# APRS_Pico_with_Baofeng_UV-5R.net
KiCad netlist of a schematic drawn in EAGLE
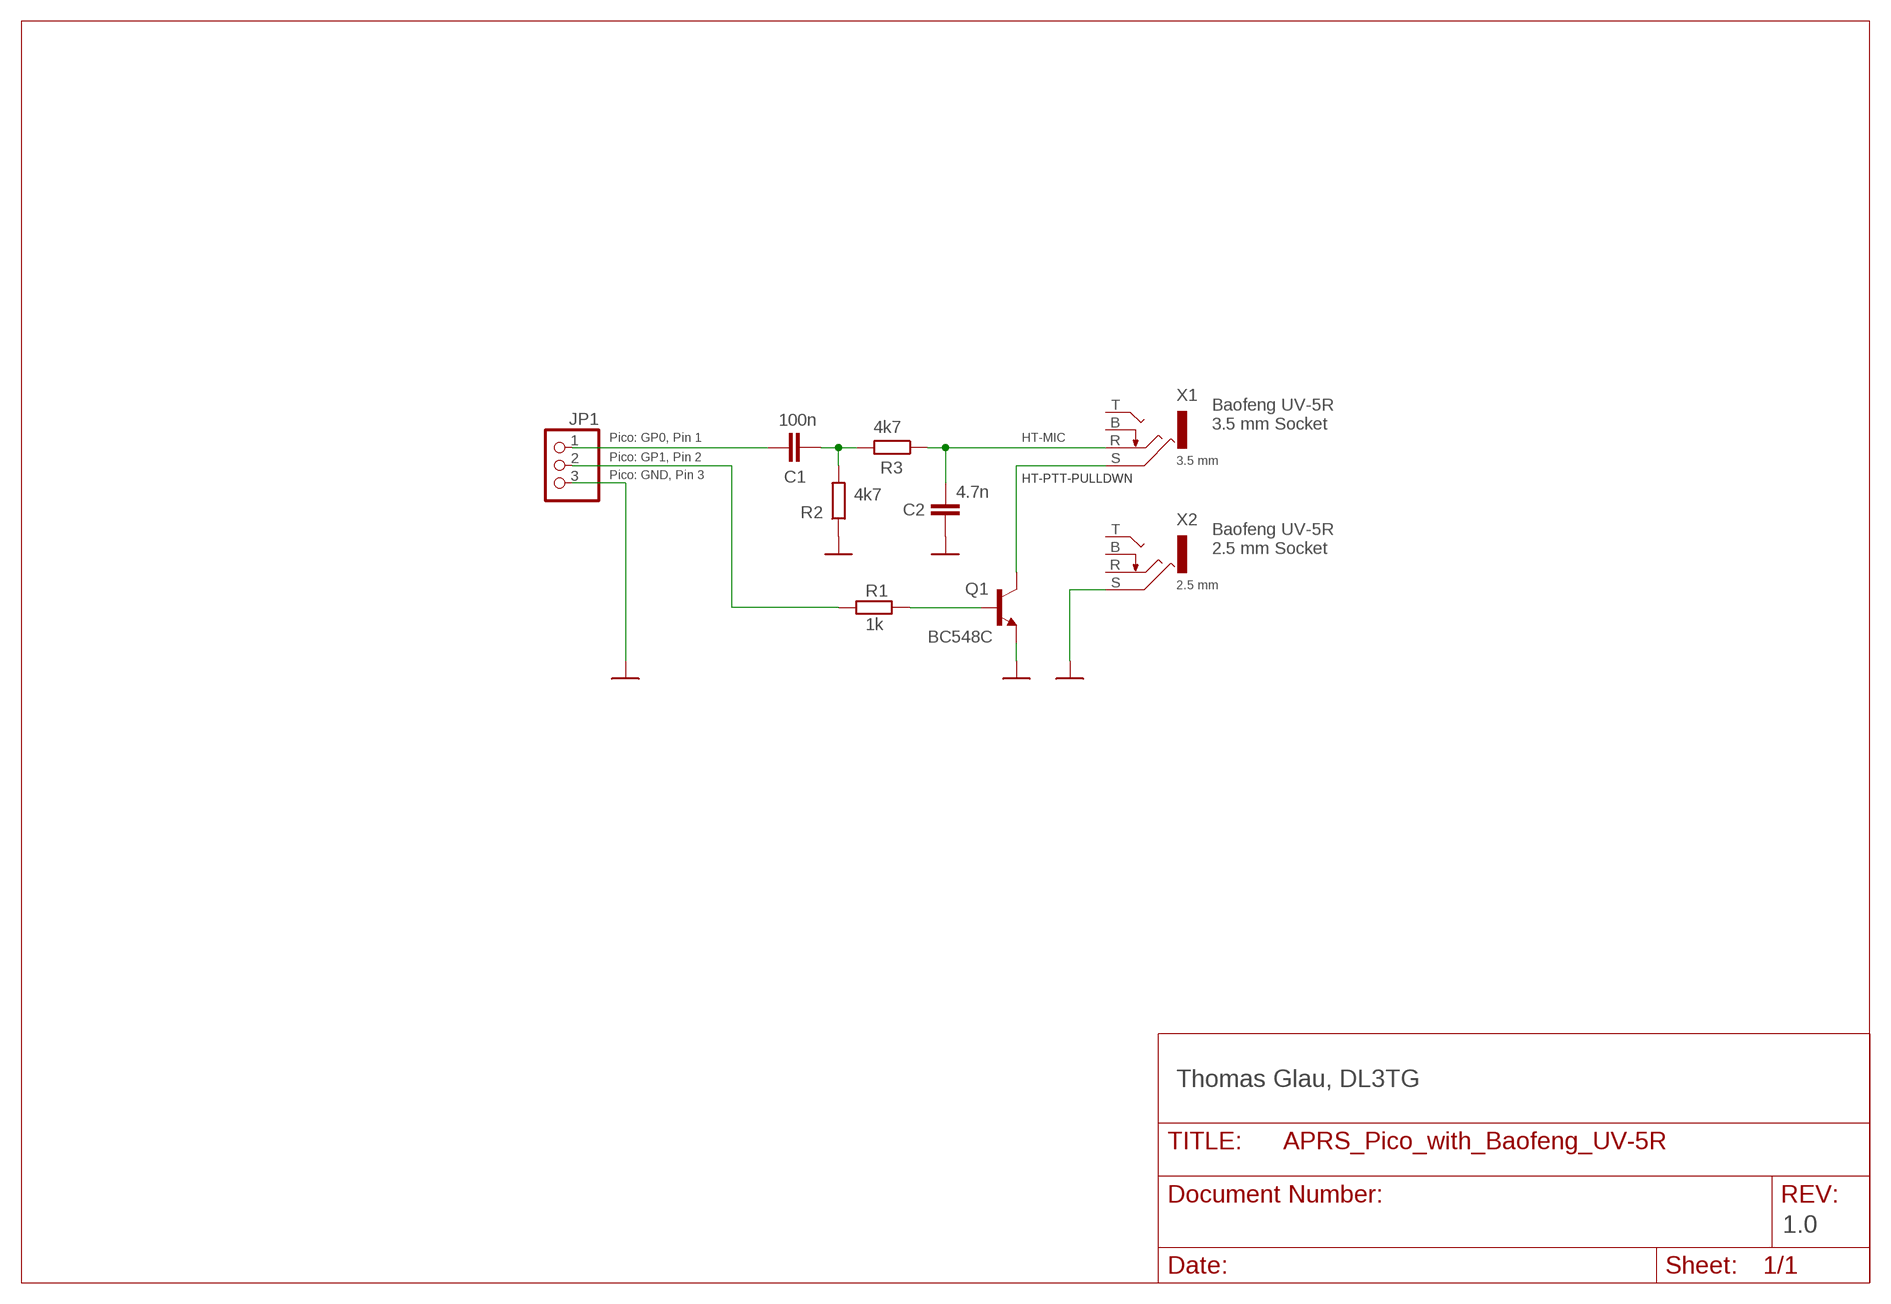
[diagram p0: schematic, sheet 1]

(export (version "E")
  (design (tool "Eeschema 10.0.6"))
  (components
    (comp (ref "C1")
      (value "100n")
      (footprint "eagle-import:C0805")
      (libsource (lib "eagle-import") (part "C"))
    )
    (comp (ref "C2")
      (value "4.7n")
      (footprint "eagle-import:C0805")
      (libsource (lib "eagle-import") (part "C"))
    )
    (comp (ref "JP1")
      (value "PINHD-1X3")
      (footprint "eagle-import:1X03")
      (libsource (lib "eagle-import") (part "PINHD-1X3"))
    )
    (comp (ref "Q1")
      (value "BC548C")
      (footprint "eagle-import:TO92-EBC")
      (libsource (lib "eagle-import") (part "BC548"))
    )
    (comp (ref "R1")
      (value "1k")
      (footprint "eagle-import:0207_10")
      (libsource (lib "eagle-import") (part "R-EU_0207/10"))
    )
    (comp (ref "R2")
      (value "4k7")
      (footprint "eagle-import:R0805")
      (libsource (lib "eagle-import") (part "R"))
    )
    (comp (ref "R3")
      (value "4k7")
      (footprint "eagle-import:R0805")
      (libsource (lib "eagle-import") (part "R"))
    )
    (comp (ref "X1")
      (value "KLBR4")
      (footprint "eagle-import:KLBR4")
      (fields (field (name "MPN") "KLBR 4"))
      (libsource (lib "eagle-import") (part "KLBR4"))
    )
    (comp (ref "X2")
      (value "KLBR4")
      (footprint "eagle-import:KLBR4")
      (fields (field (name "MPN") "KLBR 4"))
      (libsource (lib "eagle-import") (part "KLBR4"))
    )
  )
  (nets
    (net (code "1") (name "/HT-PTT-PULLDWN") (class "Default")
      (node (ref "Q1") (pin "C") (pinfunction "C_C") (pintype "passive"))
      (node (ref "X1") (pin "S") (pinfunction "S_S") (pintype "passive"))
    )
    (net (code "2") (name "GND") (class "Default")
      (node (ref "C2") (pin "1") (pinfunction "1_1") (pintype "passive"))
      (node (ref "JP1") (pin "3") (pinfunction "3_3") (pintype "passive"))
      (node (ref "Q1") (pin "E") (pinfunction "E_E") (pintype "passive"))
      (node (ref "R2") (pin "1") (pinfunction "1_1") (pintype "passive"))
      (node (ref "X2") (pin "S") (pinfunction "S_S") (pintype "passive"))
    )
    (net (code "3") (name "Net-(C1-Pad1)") (class "Default")
      (node (ref "C1") (pin "1") (pinfunction "1_1") (pintype "passive"))
      (node (ref "JP1") (pin "1") (pinfunction "1_1") (pintype "passive"))
    )
    (net (code "4") (name "Net-(C1-Pad2)") (class "Default")
      (node (ref "C1") (pin "2") (pinfunction "2_2") (pintype "passive"))
      (node (ref "R2") (pin "2") (pinfunction "2_2") (pintype "passive"))
      (node (ref "R3") (pin "2") (pinfunction "2_2") (pintype "passive"))
    )
    (net (code "5") (name "Net-(C2-Pad2)") (class "Default")
      (node (ref "C2") (pin "2") (pinfunction "2_2") (pintype "passive"))
      (node (ref "R3") (pin "1") (pinfunction "1_1") (pintype "passive"))
      (node (ref "X1") (pin "R") (pinfunction "R_R") (pintype "passive"))
    )
    (net (code "6") (name "Net-(JP1-Pad2)") (class "Default")
      (node (ref "JP1") (pin "2") (pinfunction "2_2") (pintype "passive"))
      (node (ref "R1") (pin "1") (pinfunction "1_1") (pintype "passive"))
    )
    (net (code "7") (name "Net-(Q1-PadB)") (class "Default")
      (node (ref "Q1") (pin "B") (pinfunction "B_B") (pintype "passive"))
      (node (ref "R1") (pin "2") (pinfunction "2_2") (pintype "passive"))
    )
    (net (code "8") (name "unconnected-(X1-PadB)") (class "Default")
      (node (ref "X1") (pin "B") (pinfunction "B_B") (pintype "passive"))
    )
    (net (code "9") (name "unconnected-(X1-PadT)") (class "Default")
      (node (ref "X1") (pin "T") (pinfunction "T_T") (pintype "passive"))
    )
    (net (code "10") (name "unconnected-(X2-PadB)") (class "Default")
      (node (ref "X2") (pin "B") (pinfunction "B_B") (pintype "passive"))
    )
    (net (code "11") (name "unconnected-(X2-PadR)") (class "Default")
      (node (ref "X2") (pin "R") (pinfunction "R_R") (pintype "passive"))
    )
    (net (code "12") (name "unconnected-(X2-PadT)") (class "Default")
      (node (ref "X2") (pin "T") (pinfunction "T_T") (pintype "passive"))
    )
  )
)
